# IO-testing-mezzanine.net
KiCad netlist of a schematic drawn in Altium Designer
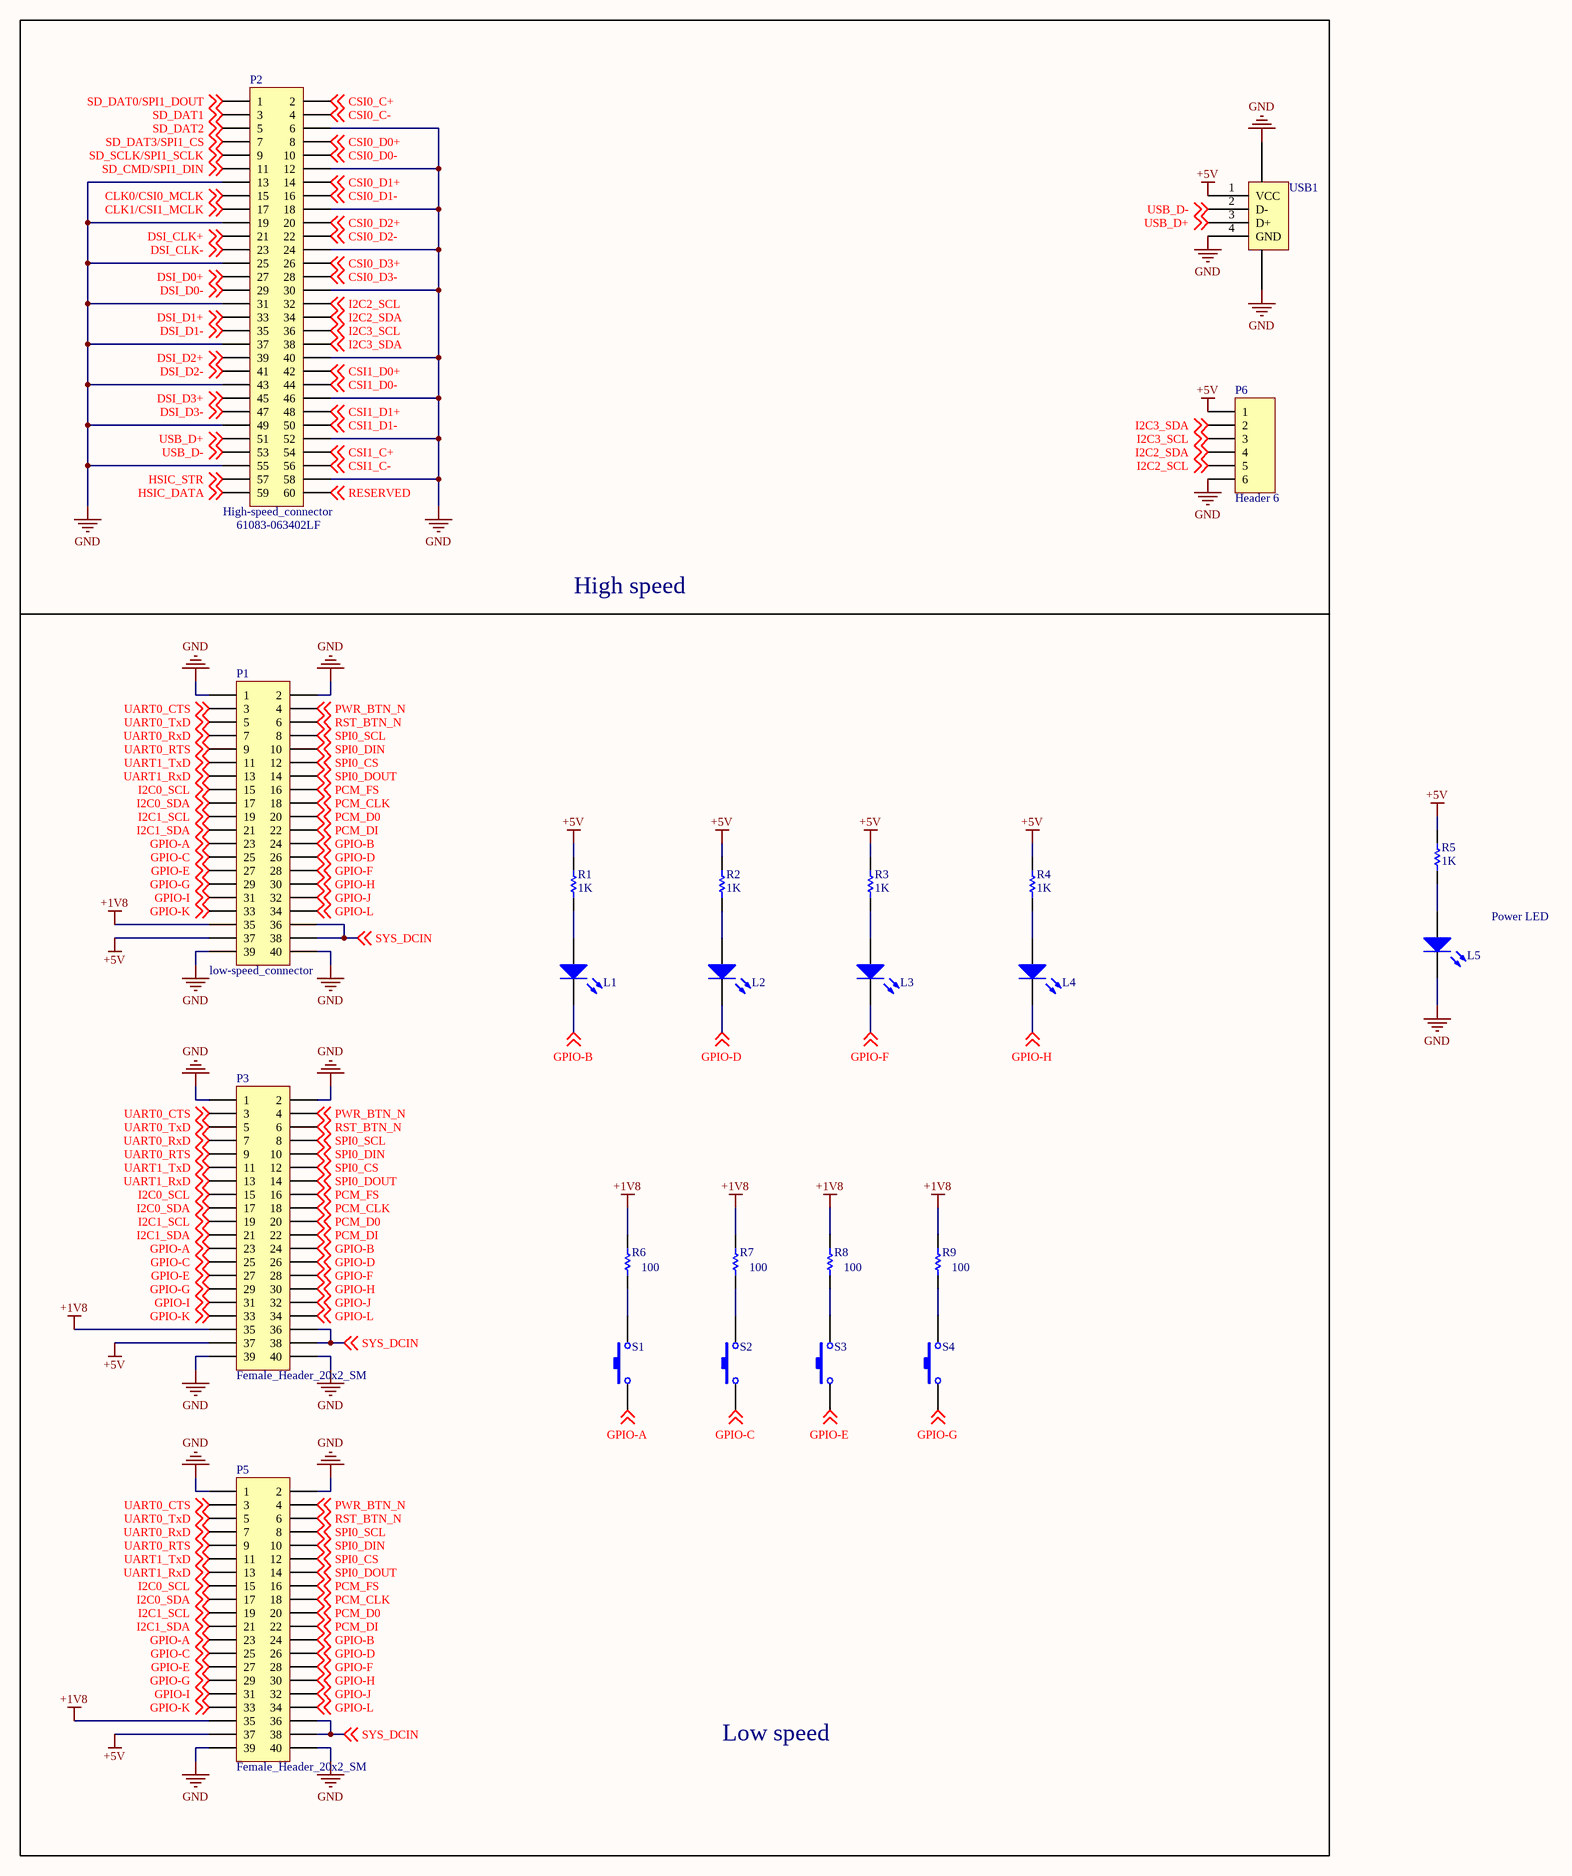
[diagram p0: IO-testing-mezzanine.SchDoc]

(export (version "E")
  (design (tool "Eeschema 10.0.6"))
  (components
    (comp (ref "L1")
      (value "~")
      (footprint "LED_0603")
      (description "LED BLUE CLEAR 0603 SMD")
      (fields
        (field (name "MANUFACTURER") "Lite-On Inc.")
        (field (name "MANUFACTURER PART NUMBER") "LTST-C193TBKT-5A")
      )
      (libsource (lib "IO-testing-mezzanine") (part "LTST-C193TBKT-5A"))
    )
    (comp (ref "L2")
      (value "~")
      (footprint "LED_0603")
      (description "LED BLUE CLEAR 0603 SMD")
      (fields
        (field (name "MANUFACTURER") "Lite-On Inc.")
        (field (name "MANUFACTURER PART NUMBER") "LTST-C193TBKT-5A")
      )
      (libsource (lib "IO-testing-mezzanine") (part "LTST-C193TBKT-5A"))
    )
    (comp (ref "L3")
      (value "~")
      (footprint "LED_0603")
      (description "LED BLUE CLEAR 0603 SMD")
      (fields
        (field (name "MANUFACTURER") "Lite-On Inc.")
        (field (name "MANUFACTURER PART NUMBER") "LTST-C193TBKT-5A")
      )
      (libsource (lib "IO-testing-mezzanine") (part "LTST-C193TBKT-5A"))
    )
    (comp (ref "L4")
      (value "~")
      (footprint "LED_0603")
      (description "LED BLUE CLEAR 0603 SMD")
      (fields
        (field (name "MANUFACTURER") "Lite-On Inc.")
        (field (name "MANUFACTURER PART NUMBER") "LTST-C193TBKT-5A")
      )
      (libsource (lib "IO-testing-mezzanine") (part "LTST-C193TBKT-5A"))
    )
    (comp (ref "L5")
      (value "~")
      (footprint "LED_0603")
      (description "LED BLUE CLEAR 0603 SMD")
      (fields
        (field (name "MANUFACTURER") "Lite-On Inc.")
        (field (name "MANUFACTURER PART NUMBER") "LTST-C193TBKT-5A")
      )
      (libsource (lib "IO-testing-mezzanine") (part "LTST-C193TBKT-5A"))
    )
    (comp (ref "P1")
      (value "low-speed_connector")
      (footprint "low-speed_connector_SM")
      (libsource (lib "mezza") (part "low-speed_connector"))
    )
    (comp (ref "P2")
      (value "High-speed_connector")
      (footprint "high-speed_connector")
      (fields (field (name "PARTNUMBER") "61083-063402LF"))
      (libsource (lib "mezza") (part "High-speed_connector"))
    )
    (comp (ref "P3")
      (value "Female_Header_20x2_SM")
      (footprint "Female_Header_20x2_SM")
      (libsource (lib "IO-testing-mezzanine") (part "Female_Header_20x2_SM"))
    )
    (comp (ref "P5")
      (value "Female_Header_20x2_SM")
      (footprint "low-speed_connector_SM_top")
      (libsource (lib "IO-testing-mezzanine") (part "Female_Header_20x2_SM"))
    )
    (comp (ref "P6")
      (value "Header 6")
      (footprint "HDR1X6")
      (description "Header, 6-Pin")
      (fields (field (name "PUBLISHER") "Altium Limited"))
      (libsource (lib "Miscellaneous Connectors") (part "Header 6"))
    )
    (comp (ref "R1")
      (value "1K")
      (footprint "0603")
      (description "Resistor")
      (fields
        (field (name "PARTNUMBER") "RC0603JR-071KL")
        (field (name "Comment") "Res1")
        (field (name "PUBLISHER") "Altium Limited")
      )
      (libsource (lib "IO-testing-mezzanine") (part "Res1"))
    )
    (comp (ref "R2")
      (value "1K")
      (footprint "0603")
      (description "Resistor")
      (fields
        (field (name "PARTNUMBER") "RC0603JR-071KL")
        (field (name "Comment") "Res1")
        (field (name "PUBLISHER") "Altium Limited")
      )
      (libsource (lib "IO-testing-mezzanine") (part "Res1"))
    )
    (comp (ref "R3")
      (value "1K")
      (footprint "0603")
      (description "Resistor")
      (fields
        (field (name "PARTNUMBER") "RC0603JR-071KL")
        (field (name "Comment") "Res1")
        (field (name "PUBLISHER") "Altium Limited")
      )
      (libsource (lib "IO-testing-mezzanine") (part "Res1"))
    )
    (comp (ref "R4")
      (value "1K")
      (footprint "0603")
      (description "Resistor")
      (fields
        (field (name "PARTNUMBER") "RC0603JR-071KL")
        (field (name "Comment") "Res1")
        (field (name "PUBLISHER") "Altium Limited")
      )
      (libsource (lib "IO-testing-mezzanine") (part "Res1"))
    )
    (comp (ref "R5")
      (value "1K")
      (footprint "0603")
      (description "Resistor")
      (fields
        (field (name "PARTNUMBER") "RC0603JR-071KL")
        (field (name "Comment") "Res1")
        (field (name "PUBLISHER") "Altium Limited")
      )
      (libsource (lib "IO-testing-mezzanine") (part "Res1"))
    )
    (comp (ref "R6")
      (value "100")
      (footprint "0603")
      (description "Resistor")
      (fields
        (field (name "MANUFACTURER") "Yageo")
        (field (name "MANUFACTURER PART NUMBER") "RC0603JR-07100RL")
      )
      (libsource (lib "IO-testing-mezzanine") (part "Res1"))
    )
    (comp (ref "R7")
      (value "100")
      (footprint "0603")
      (description "Resistor")
      (fields
        (field (name "MANUFACTURER") "Yageo")
        (field (name "MANUFACTURER PART NUMBER") "RC0603JR-07100RL")
      )
      (libsource (lib "IO-testing-mezzanine") (part "Res1"))
    )
    (comp (ref "R8")
      (value "100")
      (footprint "0603")
      (description "Resistor")
      (fields
        (field (name "MANUFACTURER") "Yageo")
        (field (name "MANUFACTURER PART NUMBER") "RC0603JR-07100RL")
      )
      (libsource (lib "IO-testing-mezzanine") (part "Res1"))
    )
    (comp (ref "R9")
      (value "100")
      (footprint "0603")
      (description "Resistor")
      (fields
        (field (name "MANUFACTURER") "Yageo")
        (field (name "MANUFACTURER PART NUMBER") "RC0603JR-07100RL")
      )
      (libsource (lib "IO-testing-mezzanine") (part "Res1"))
    )
    (comp (ref "S1")
      (value "SW-PB")
      (footprint "SW-PB")
      (description "Switch")
      (fields
        (field (name "MANUFACTURER") "C&K")
        (field (name "MANUFACTURER PART NUMBER") "KSR223GLFG")
        (field (name "PUBLISHER") "Altium Limited")
      )
      (libsource (lib "IO-testing-mezzanine") (part "SW-PB"))
    )
    (comp (ref "S2")
      (value "SW-PB")
      (footprint "SW-PB")
      (description "Switch")
      (fields
        (field (name "MANUFACTURER") "C&K")
        (field (name "MANUFACTURER PART NUMBER") "KSR223GLFG")
        (field (name "PUBLISHER") "Altium Limited")
      )
      (libsource (lib "IO-testing-mezzanine") (part "SW-PB"))
    )
    (comp (ref "S3")
      (value "SW-PB")
      (footprint "SW-PB")
      (description "Switch")
      (fields
        (field (name "MANUFACTURER") "C&K")
        (field (name "MANUFACTURER PART NUMBER") "KSR223GLFG")
        (field (name "PUBLISHER") "Altium Limited")
      )
      (libsource (lib "IO-testing-mezzanine") (part "SW-PB"))
    )
    (comp (ref "S4")
      (value "SW-PB")
      (footprint "SW-PB")
      (description "Switch")
      (fields
        (field (name "MANUFACTURER") "C&K")
        (field (name "MANUFACTURER PART NUMBER") "KSR223GLFG")
        (field (name "PUBLISHER") "Altium Limited")
      )
      (libsource (lib "IO-testing-mezzanine") (part "SW-PB"))
    )
    (comp (ref "USB1")
      (value "USB")
      (footprint "USB_a")
      (fields (field (name "PARTNUMBER") "USB-A-S-F-W-SM2") (field (name "MANUFACTURER") "Samtec Inc."))
      (libsource (lib "IO-testing-mezzanine") (part "USB"))
    )
  )
  (nets
    (net (code "1") (name "+1V8") (class "Default")
      (node (ref "P1") (pin "35") (pinfunction "35_35") (pintype "passive"))
      (node (ref "P3") (pin "35") (pinfunction "35_35") (pintype "passive"))
      (node (ref "P5") (pin "35") (pinfunction "35_35") (pintype "passive"))
      (node (ref "R6") (pin "2") (pinfunction "2_2") (pintype "passive"))
      (node (ref "R7") (pin "2") (pinfunction "2_2") (pintype "passive"))
      (node (ref "R8") (pin "2") (pinfunction "2_2") (pintype "passive"))
      (node (ref "R9") (pin "2") (pinfunction "2_2") (pintype "passive"))
    )
    (net (code "2") (name "+5V") (class "Default")
      (node (ref "P1") (pin "37") (pinfunction "37_37") (pintype "passive"))
      (node (ref "P3") (pin "37") (pinfunction "37_37") (pintype "passive"))
      (node (ref "P5") (pin "37") (pinfunction "37_37") (pintype "passive"))
      (node (ref "P6") (pin "1") (pinfunction "1_1") (pintype "passive"))
      (node (ref "R1") (pin "2") (pinfunction "2_2") (pintype "passive"))
      (node (ref "R2") (pin "2") (pinfunction "2_2") (pintype "passive"))
      (node (ref "R3") (pin "2") (pinfunction "2_2") (pintype "passive"))
      (node (ref "R4") (pin "2") (pinfunction "2_2") (pintype "passive"))
      (node (ref "R5") (pin "2") (pinfunction "2_2") (pintype "passive"))
      (node (ref "USB1") (pin "1") (pinfunction "VCC_1") (pintype "power_in"))
    )
    (net (code "3") (name "CLK0{slash}CSI0_MCLK") (class "Default")
      (node (ref "P2") (pin "15") (pinfunction "15_15") (pintype "passive"))
    )
    (net (code "4") (name "CLK1{slash}CSI1_MCLK") (class "Default")
      (node (ref "P2") (pin "17") (pinfunction "17_17") (pintype "passive"))
    )
    (net (code "5") (name "CSI0_C+") (class "Default")
      (node (ref "P2") (pin "2") (pinfunction "2_2") (pintype "passive"))
    )
    (net (code "6") (name "CSI0_C-") (class "Default")
      (node (ref "P2") (pin "4") (pinfunction "4_4") (pintype "passive"))
    )
    (net (code "7") (name "CSI0_D0+") (class "Default")
      (node (ref "P2") (pin "8") (pinfunction "8_8") (pintype "passive"))
    )
    (net (code "8") (name "CSI0_D0-") (class "Default")
      (node (ref "P2") (pin "10") (pinfunction "10_10") (pintype "passive"))
    )
    (net (code "9") (name "CSI0_D1+") (class "Default")
      (node (ref "P2") (pin "14") (pinfunction "14_14") (pintype "passive"))
    )
    (net (code "10") (name "CSI0_D1-") (class "Default")
      (node (ref "P2") (pin "16") (pinfunction "16_16") (pintype "passive"))
    )
    (net (code "11") (name "CSI0_D2+") (class "Default")
      (node (ref "P2") (pin "20") (pinfunction "20_20") (pintype "passive"))
    )
    (net (code "12") (name "CSI0_D2-") (class "Default")
      (node (ref "P2") (pin "22") (pinfunction "22_22") (pintype "passive"))
    )
    (net (code "13") (name "CSI0_D3+") (class "Default")
      (node (ref "P2") (pin "26") (pinfunction "26_26") (pintype "passive"))
    )
    (net (code "14") (name "CSI0_D3-") (class "Default")
      (node (ref "P2") (pin "28") (pinfunction "28_28") (pintype "passive"))
    )
    (net (code "15") (name "CSI1_C+") (class "Default")
      (node (ref "P2") (pin "54") (pinfunction "54_54") (pintype "passive"))
    )
    (net (code "16") (name "CSI1_C-") (class "Default")
      (node (ref "P2") (pin "56") (pinfunction "56_56") (pintype "passive"))
    )
    (net (code "17") (name "CSI1_D0+") (class "Default")
      (node (ref "P2") (pin "42") (pinfunction "42_42") (pintype "passive"))
    )
    (net (code "18") (name "CSI1_D0-") (class "Default")
      (node (ref "P2") (pin "44") (pinfunction "44_44") (pintype "passive"))
    )
    (net (code "19") (name "CSI1_D1+") (class "Default")
      (node (ref "P2") (pin "48") (pinfunction "48_48") (pintype "passive"))
    )
    (net (code "20") (name "CSI1_D1-") (class "Default")
      (node (ref "P2") (pin "50") (pinfunction "50_50") (pintype "passive"))
    )
    (net (code "21") (name "DSI_CLK+") (class "Default")
      (node (ref "P2") (pin "21") (pinfunction "21_21") (pintype "passive"))
    )
    (net (code "22") (name "DSI_CLK-") (class "Default")
      (node (ref "P2") (pin "23") (pinfunction "23_23") (pintype "passive"))
    )
    (net (code "23") (name "DSI_D0+") (class "Default")
      (node (ref "P2") (pin "27") (pinfunction "27_27") (pintype "passive"))
    )
    (net (code "24") (name "DSI_D0-") (class "Default")
      (node (ref "P2") (pin "29") (pinfunction "29_29") (pintype "passive"))
    )
    (net (code "25") (name "DSI_D1+") (class "Default")
      (node (ref "P2") (pin "33") (pinfunction "33_33") (pintype "passive"))
    )
    (net (code "26") (name "DSI_D1-") (class "Default")
      (node (ref "P2") (pin "35") (pinfunction "35_35") (pintype "passive"))
    )
    (net (code "27") (name "DSI_D2+") (class "Default")
      (node (ref "P2") (pin "39") (pinfunction "39_39") (pintype "passive"))
    )
    (net (code "28") (name "DSI_D2-") (class "Default")
      (node (ref "P2") (pin "41") (pinfunction "41_41") (pintype "passive"))
    )
    (net (code "29") (name "DSI_D3+") (class "Default")
      (node (ref "P2") (pin "45") (pinfunction "45_45") (pintype "passive"))
    )
    (net (code "30") (name "DSI_D3-") (class "Default")
      (node (ref "P2") (pin "47") (pinfunction "47_47") (pintype "passive"))
    )
    (net (code "31") (name "GND") (class "Default")
      (node (ref "L5") (pin "2") (pinfunction "K_2") (pintype "passive"))
      (node (ref "P1") (pin "1") (pinfunction "1_1") (pintype "passive"))
      (node (ref "P1") (pin "2") (pinfunction "2_2") (pintype "passive"))
      (node (ref "P1") (pin "39") (pinfunction "39_39") (pintype "passive"))
      (node (ref "P1") (pin "40") (pinfunction "40_40") (pintype "passive"))
      (node (ref "P2") (pin "12") (pinfunction "12_12") (pintype "passive"))
      (node (ref "P2") (pin "13") (pinfunction "13_13") (pintype "passive"))
      (node (ref "P2") (pin "18") (pinfunction "18_18") (pintype "passive"))
      (node (ref "P2") (pin "19") (pinfunction "19_19") (pintype "passive"))
      (node (ref "P2") (pin "24") (pinfunction "24_24") (pintype "passive"))
      (node (ref "P2") (pin "25") (pinfunction "25_25") (pintype "passive"))
      (node (ref "P2") (pin "30") (pinfunction "30_30") (pintype "passive"))
      (node (ref "P2") (pin "31") (pinfunction "31_31") (pintype "passive"))
      (node (ref "P2") (pin "37") (pinfunction "37_37") (pintype "passive"))
      (node (ref "P2") (pin "40") (pinfunction "40_40") (pintype "passive"))
      (node (ref "P2") (pin "43") (pinfunction "43_43") (pintype "passive"))
      (node (ref "P2") (pin "46") (pinfunction "46_46") (pintype "passive"))
      (node (ref "P2") (pin "49") (pinfunction "49_49") (pintype "passive"))
      (node (ref "P2") (pin "52") (pinfunction "52_52") (pintype "passive"))
      (node (ref "P2") (pin "55") (pinfunction "55_55") (pintype "passive"))
      (node (ref "P2") (pin "58") (pinfunction "58_58") (pintype "passive"))
      (node (ref "P2") (pin "6") (pinfunction "6_6") (pintype "passive"))
      (node (ref "P3") (pin "1") (pinfunction "1_1") (pintype "passive"))
      (node (ref "P3") (pin "2") (pinfunction "2_2") (pintype "passive"))
      (node (ref "P3") (pin "39") (pinfunction "39_39") (pintype "passive"))
      (node (ref "P3") (pin "40") (pinfunction "40_40") (pintype "passive"))
      (node (ref "P5") (pin "1") (pinfunction "1_1") (pintype "passive"))
      (node (ref "P5") (pin "2") (pinfunction "2_2") (pintype "passive"))
      (node (ref "P5") (pin "39") (pinfunction "39_39") (pintype "passive"))
      (node (ref "P5") (pin "40") (pinfunction "40_40") (pintype "passive"))
      (node (ref "P6") (pin "6") (pinfunction "6_6") (pintype "passive"))
      (node (ref "USB1") (pin "4") (pinfunction "GND_4") (pintype "power_in"))
      (node (ref "USB1") (pin "5") (pinfunction "GND_5") (pintype "power_in"))
      (node (ref "USB1") (pin "6") (pinfunction "GND_6") (pintype "power_in"))
    )
    (net (code "32") (name "GPIO-A") (class "Default")
      (node (ref "P1") (pin "23") (pinfunction "23_23") (pintype "passive"))
      (node (ref "P3") (pin "23") (pinfunction "23_23") (pintype "passive"))
      (node (ref "P5") (pin "23") (pinfunction "23_23") (pintype "passive"))
      (node (ref "S1") (pin "1") (pinfunction "1_1") (pintype "passive"))
    )
    (net (code "33") (name "GPIO-B") (class "Default")
      (node (ref "L1") (pin "2") (pinfunction "K_2") (pintype "passive"))
      (node (ref "P1") (pin "24") (pinfunction "24_24") (pintype "passive"))
      (node (ref "P3") (pin "24") (pinfunction "24_24") (pintype "passive"))
      (node (ref "P5") (pin "24") (pinfunction "24_24") (pintype "passive"))
    )
    (net (code "34") (name "GPIO-C") (class "Default")
      (node (ref "P1") (pin "25") (pinfunction "25_25") (pintype "passive"))
      (node (ref "P3") (pin "25") (pinfunction "25_25") (pintype "passive"))
      (node (ref "P5") (pin "25") (pinfunction "25_25") (pintype "passive"))
      (node (ref "S2") (pin "1") (pinfunction "1_1") (pintype "passive"))
    )
    (net (code "35") (name "GPIO-D") (class "Default")
      (node (ref "L2") (pin "2") (pinfunction "K_2") (pintype "passive"))
      (node (ref "P1") (pin "26") (pinfunction "26_26") (pintype "passive"))
      (node (ref "P3") (pin "26") (pinfunction "26_26") (pintype "passive"))
      (node (ref "P5") (pin "26") (pinfunction "26_26") (pintype "passive"))
    )
    (net (code "36") (name "GPIO-E") (class "Default")
      (node (ref "P1") (pin "27") (pinfunction "27_27") (pintype "passive"))
      (node (ref "P3") (pin "27") (pinfunction "27_27") (pintype "passive"))
      (node (ref "P5") (pin "27") (pinfunction "27_27") (pintype "passive"))
      (node (ref "S3") (pin "1") (pinfunction "1_1") (pintype "passive"))
    )
    (net (code "37") (name "GPIO-F") (class "Default")
      (node (ref "L3") (pin "2") (pinfunction "K_2") (pintype "passive"))
      (node (ref "P1") (pin "28") (pinfunction "28_28") (pintype "passive"))
      (node (ref "P3") (pin "28") (pinfunction "28_28") (pintype "passive"))
      (node (ref "P5") (pin "28") (pinfunction "28_28") (pintype "passive"))
    )
    (net (code "38") (name "GPIO-G") (class "Default")
      (node (ref "P1") (pin "29") (pinfunction "29_29") (pintype "passive"))
      (node (ref "P3") (pin "29") (pinfunction "29_29") (pintype "passive"))
      (node (ref "P5") (pin "29") (pinfunction "29_29") (pintype "passive"))
      (node (ref "S4") (pin "1") (pinfunction "1_1") (pintype "passive"))
    )
    (net (code "39") (name "GPIO-H") (class "Default")
      (node (ref "L4") (pin "2") (pinfunction "K_2") (pintype "passive"))
      (node (ref "P1") (pin "30") (pinfunction "30_30") (pintype "passive"))
      (node (ref "P3") (pin "30") (pinfunction "30_30") (pintype "passive"))
      (node (ref "P5") (pin "30") (pinfunction "30_30") (pintype "passive"))
    )
    (net (code "40") (name "GPIO-I") (class "Default")
      (node (ref "P1") (pin "31") (pinfunction "31_31") (pintype "passive"))
      (node (ref "P3") (pin "31") (pinfunction "31_31") (pintype "passive"))
      (node (ref "P5") (pin "31") (pinfunction "31_31") (pintype "passive"))
    )
    (net (code "41") (name "GPIO-J") (class "Default")
      (node (ref "P1") (pin "32") (pinfunction "32_32") (pintype "passive"))
      (node (ref "P3") (pin "32") (pinfunction "32_32") (pintype "passive"))
      (node (ref "P5") (pin "32") (pinfunction "32_32") (pintype "passive"))
    )
    (net (code "42") (name "GPIO-K") (class "Default")
      (node (ref "P1") (pin "33") (pinfunction "33_33") (pintype "passive"))
      (node (ref "P3") (pin "33") (pinfunction "33_33") (pintype "passive"))
      (node (ref "P5") (pin "33") (pinfunction "33_33") (pintype "passive"))
    )
    (net (code "43") (name "GPIO-L") (class "Default")
      (node (ref "P1") (pin "34") (pinfunction "34_34") (pintype "passive"))
      (node (ref "P3") (pin "34") (pinfunction "34_34") (pintype "passive"))
      (node (ref "P5") (pin "34") (pinfunction "34_34") (pintype "passive"))
    )
    (net (code "44") (name "HSIC_DATA") (class "Default")
      (node (ref "P2") (pin "59") (pinfunction "59_59") (pintype "passive"))
    )
    (net (code "45") (name "HSIC_STR") (class "Default")
      (node (ref "P2") (pin "39") (pinfunction "57_39") (pintype "passive"))
    )
    (net (code "46") (name "I2C0_SCL") (class "Default")
      (node (ref "P1") (pin "15") (pinfunction "15_15") (pintype "passive"))
      (node (ref "P3") (pin "15") (pinfunction "15_15") (pintype "passive"))
      (node (ref "P5") (pin "15") (pinfunction "15_15") (pintype "passive"))
    )
    (net (code "47") (name "I2C0_SDA") (class "Default")
      (node (ref "P1") (pin "17") (pinfunction "17_17") (pintype "passive"))
      (node (ref "P3") (pin "17") (pinfunction "17_17") (pintype "passive"))
      (node (ref "P5") (pin "17") (pinfunction "17_17") (pintype "passive"))
    )
    (net (code "48") (name "I2C1_SCL") (class "Default")
      (node (ref "P1") (pin "19") (pinfunction "19_19") (pintype "passive"))
      (node (ref "P3") (pin "19") (pinfunction "19_19") (pintype "passive"))
      (node (ref "P5") (pin "19") (pinfunction "19_19") (pintype "passive"))
    )
    (net (code "49") (name "I2C1_SDA") (class "Default")
      (node (ref "P1") (pin "21") (pinfunction "21_21") (pintype "passive"))
      (node (ref "P3") (pin "21") (pinfunction "21_21") (pintype "passive"))
      (node (ref "P5") (pin "21") (pinfunction "21_21") (pintype "passive"))
    )
    (net (code "50") (name "I2C2_SCL") (class "Default")
      (node (ref "P2") (pin "32") (pinfunction "32_32") (pintype "passive"))
      (node (ref "P6") (pin "5") (pinfunction "5_5") (pintype "passive"))
    )
    (net (code "51") (name "I2C2_SDA") (class "Default")
      (node (ref "P2") (pin "34") (pinfunction "34_34") (pintype "passive"))
      (node (ref "P6") (pin "4") (pinfunction "4_4") (pintype "passive"))
    )
    (net (code "52") (name "I2C3_SCL") (class "Default")
      (node (ref "P2") (pin "36") (pinfunction "36_36") (pintype "passive"))
      (node (ref "P6") (pin "3") (pinfunction "3_3") (pintype "passive"))
    )
    (net (code "53") (name "I2C3_SDA") (class "Default")
      (node (ref "P2") (pin "38") (pinfunction "38_38") (pintype "passive"))
      (node (ref "P6") (pin "2") (pinfunction "2_2") (pintype "passive"))
    )
    (net (code "54") (name "Net-(L1-A)") (class "Default")
      (node (ref "L1") (pin "1") (pinfunction "A_1") (pintype "passive"))
      (node (ref "R1") (pin "1") (pinfunction "1_1") (pintype "passive"))
    )
    (net (code "55") (name "Net-(L2-A)") (class "Default")
      (node (ref "L2") (pin "1") (pinfunction "A_1") (pintype "passive"))
      (node (ref "R2") (pin "1") (pinfunction "1_1") (pintype "passive"))
    )
    (net (code "56") (name "Net-(L3-A)") (class "Default")
      (node (ref "L3") (pin "1") (pinfunction "A_1") (pintype "passive"))
      (node (ref "R3") (pin "1") (pinfunction "1_1") (pintype "passive"))
    )
    (net (code "57") (name "Net-(L4-A)") (class "Default")
      (node (ref "L4") (pin "1") (pinfunction "A_1") (pintype "passive"))
      (node (ref "R4") (pin "1") (pinfunction "1_1") (pintype "passive"))
    )
    (net (code "58") (name "Net-(L5-A)") (class "Default")
      (node (ref "L5") (pin "1") (pinfunction "A_1") (pintype "passive"))
      (node (ref "R5") (pin "1") (pinfunction "1_1") (pintype "passive"))
    )
    (net (code "59") (name "Net-(R6-Pad1)") (class "Default")
      (node (ref "R6") (pin "1") (pinfunction "1_1") (pintype "passive"))
      (node (ref "S1") (pin "2") (pinfunction "2_2") (pintype "passive"))
    )
    (net (code "60") (name "Net-(R7-Pad1)") (class "Default")
      (node (ref "R7") (pin "1") (pinfunction "1_1") (pintype "passive"))
      (node (ref "S2") (pin "2") (pinfunction "2_2") (pintype "passive"))
    )
    (net (code "61") (name "Net-(R8-Pad1)") (class "Default")
      (node (ref "R8") (pin "1") (pinfunction "1_1") (pintype "passive"))
      (node (ref "S3") (pin "2") (pinfunction "2_2") (pintype "passive"))
    )
    (net (code "62") (name "Net-(R9-Pad1)") (class "Default")
      (node (ref "R9") (pin "1") (pinfunction "1_1") (pintype "passive"))
      (node (ref "S4") (pin "2") (pinfunction "2_2") (pintype "passive"))
    )
    (net (code "63") (name "PCM_CLK") (class "Default")
      (node (ref "P1") (pin "18") (pinfunction "18_18") (pintype "passive"))
      (node (ref "P3") (pin "18") (pinfunction "18_18") (pintype "passive"))
      (node (ref "P5") (pin "18") (pinfunction "18_18") (pintype "passive"))
    )
    (net (code "64") (name "PCM_D0") (class "Default")
      (node (ref "P1") (pin "20") (pinfunction "20_20") (pintype "passive"))
      (node (ref "P3") (pin "20") (pinfunction "20_20") (pintype "passive"))
      (node (ref "P5") (pin "20") (pinfunction "20_20") (pintype "passive"))
    )
    (net (code "65") (name "PCM_DI") (class "Default")
      (node (ref "P1") (pin "22") (pinfunction "22_22") (pintype "passive"))
      (node (ref "P3") (pin "22") (pinfunction "22_22") (pintype "passive"))
      (node (ref "P5") (pin "22") (pinfunction "22_22") (pintype "passive"))
    )
    (net (code "66") (name "PCM_FS") (class "Default")
      (node (ref "P1") (pin "16") (pinfunction "16_16") (pintype "passive"))
      (node (ref "P3") (pin "16") (pinfunction "16_16") (pintype "passive"))
      (node (ref "P5") (pin "16") (pinfunction "16_16") (pintype "passive"))
    )
    (net (code "67") (name "PWR_BTN_N") (class "Default")
      (node (ref "P1") (pin "4") (pinfunction "4_4") (pintype "passive"))
      (node (ref "P3") (pin "4") (pinfunction "4_4") (pintype "passive"))
      (node (ref "P5") (pin "4") (pinfunction "4_4") (pintype "passive"))
    )
    (net (code "68") (name "RESERVED") (class "Default")
      (node (ref "P2") (pin "38") (pinfunction "60_38") (pintype "passive"))
    )
    (net (code "69") (name "RST_BTN_N") (class "Default")
      (node (ref "P1") (pin "6") (pinfunction "6_6") (pintype "passive"))
      (node (ref "P3") (pin "6") (pinfunction "6_6") (pintype "passive"))
      (node (ref "P5") (pin "6") (pinfunction "6_6") (pintype "passive"))
    )
    (net (code "70") (name "SD_CMD{slash}SPI1_DIN") (class "Default")
      (node (ref "P2") (pin "11") (pinfunction "11_11") (pintype "passive"))
    )
    (net (code "71") (name "SD_DAT0{slash}SPI1_DOUT") (class "Default")
      (node (ref "P2") (pin "1") (pinfunction "1_1") (pintype "passive"))
    )
    (net (code "72") (name "SD_DAT1") (class "Default")
      (node (ref "P2") (pin "3") (pinfunction "3_3") (pintype "passive"))
    )
    (net (code "73") (name "SD_DAT2") (class "Default")
      (node (ref "P2") (pin "5") (pinfunction "5_5") (pintype "passive"))
    )
    (net (code "74") (name "SD_DAT3{slash}SPI1_CS") (class "Default")
      (node (ref "P2") (pin "7") (pinfunction "7_7") (pintype "passive"))
    )
    (net (code "75") (name "SD_SCLK{slash}SPI1_SCLK") (class "Default")
      (node (ref "P2") (pin "9") (pinfunction "9_9") (pintype "passive"))
    )
    (net (code "76") (name "SPI0_CS") (class "Default")
      (node (ref "P1") (pin "12") (pinfunction "12_12") (pintype "passive"))
      (node (ref "P3") (pin "12") (pinfunction "12_12") (pintype "passive"))
      (node (ref "P5") (pin "12") (pinfunction "12_12") (pintype "passive"))
    )
    (net (code "77") (name "SPI0_DIN") (class "Default")
      (node (ref "P1") (pin "10") (pinfunction "10_10") (pintype "passive"))
      (node (ref "P3") (pin "10") (pinfunction "10_10") (pintype "passive"))
      (node (ref "P5") (pin "10") (pinfunction "10_10") (pintype "passive"))
    )
    (net (code "78") (name "SPI0_DOUT") (class "Default")
      (node (ref "P1") (pin "14") (pinfunction "14_14") (pintype "passive"))
      (node (ref "P3") (pin "14") (pinfunction "14_14") (pintype "passive"))
      (node (ref "P5") (pin "14") (pinfunction "14_14") (pintype "passive"))
    )
    (net (code "79") (name "SPI0_SCL") (class "Default")
      (node (ref "P1") (pin "8") (pinfunction "8_8") (pintype "passive"))
      (node (ref "P3") (pin "8") (pinfunction "8_8") (pintype "passive"))
      (node (ref "P5") (pin "8") (pinfunction "8_8") (pintype "passive"))
    )
    (net (code "80") (name "SYS_DCIN") (class "Default")
      (node (ref "P1") (pin "36") (pinfunction "36_36") (pintype "passive"))
      (node (ref "P1") (pin "38") (pinfunction "38_38") (pintype "passive"))
      (node (ref "P3") (pin "36") (pinfunction "36_36") (pintype "passive"))
      (node (ref "P3") (pin "38") (pinfunction "38_38") (pintype "passive"))
      (node (ref "P5") (pin "36") (pinfunction "36_36") (pintype "passive"))
      (node (ref "P5") (pin "38") (pinfunction "38_38") (pintype "passive"))
    )
    (net (code "81") (name "UART0_CTS") (class "Default")
      (node (ref "P1") (pin "3") (pinfunction "3_3") (pintype "passive"))
      (node (ref "P3") (pin "3") (pinfunction "3_3") (pintype "passive"))
      (node (ref "P5") (pin "3") (pinfunction "3_3") (pintype "passive"))
    )
    (net (code "82") (name "UART0_RTS") (class "Default")
      (node (ref "P1") (pin "9") (pinfunction "9_9") (pintype "passive"))
      (node (ref "P3") (pin "9") (pinfunction "9_9") (pintype "passive"))
      (node (ref "P5") (pin "9") (pinfunction "9_9") (pintype "passive"))
    )
    (net (code "83") (name "UART0_RxD") (class "Default")
      (node (ref "P1") (pin "7") (pinfunction "7_7") (pintype "passive"))
      (node (ref "P3") (pin "7") (pinfunction "7_7") (pintype "passive"))
      (node (ref "P5") (pin "7") (pinfunction "7_7") (pintype "passive"))
    )
    (net (code "84") (name "UART0_TxD") (class "Default")
      (node (ref "P1") (pin "5") (pinfunction "5_5") (pintype "passive"))
      (node (ref "P3") (pin "5") (pinfunction "5_5") (pintype "passive"))
      (node (ref "P5") (pin "5") (pinfunction "5_5") (pintype "passive"))
    )
    (net (code "85") (name "UART1_RxD") (class "Default")
      (node (ref "P1") (pin "13") (pinfunction "13_13") (pintype "passive"))
      (node (ref "P3") (pin "13") (pinfunction "13_13") (pintype "passive"))
      (node (ref "P5") (pin "13") (pinfunction "13_13") (pintype "passive"))
    )
    (net (code "86") (name "UART1_TxD") (class "Default")
      (node (ref "P1") (pin "11") (pinfunction "11_11") (pintype "passive"))
      (node (ref "P3") (pin "11") (pinfunction "11_11") (pintype "passive"))
      (node (ref "P5") (pin "11") (pinfunction "11_11") (pintype "passive"))
    )
    (net (code "87") (name "USB_D+") (class "Default")
      (node (ref "P2") (pin "51") (pinfunction "51_51") (pintype "passive"))
      (node (ref "USB1") (pin "3") (pinfunction "D+_3") (pintype "passive"))
    )
    (net (code "88") (name "USB_D-") (class "Default")
      (node (ref "P2") (pin "53") (pinfunction "53_53") (pintype "passive"))
      (node (ref "USB1") (pin "2") (pinfunction "D-_2") (pintype "passive"))
    )
  )
)
